# LCmeter0-LCD3310-PICCOMP.net
KiCad netlist of a schematic drawn in EAGLE
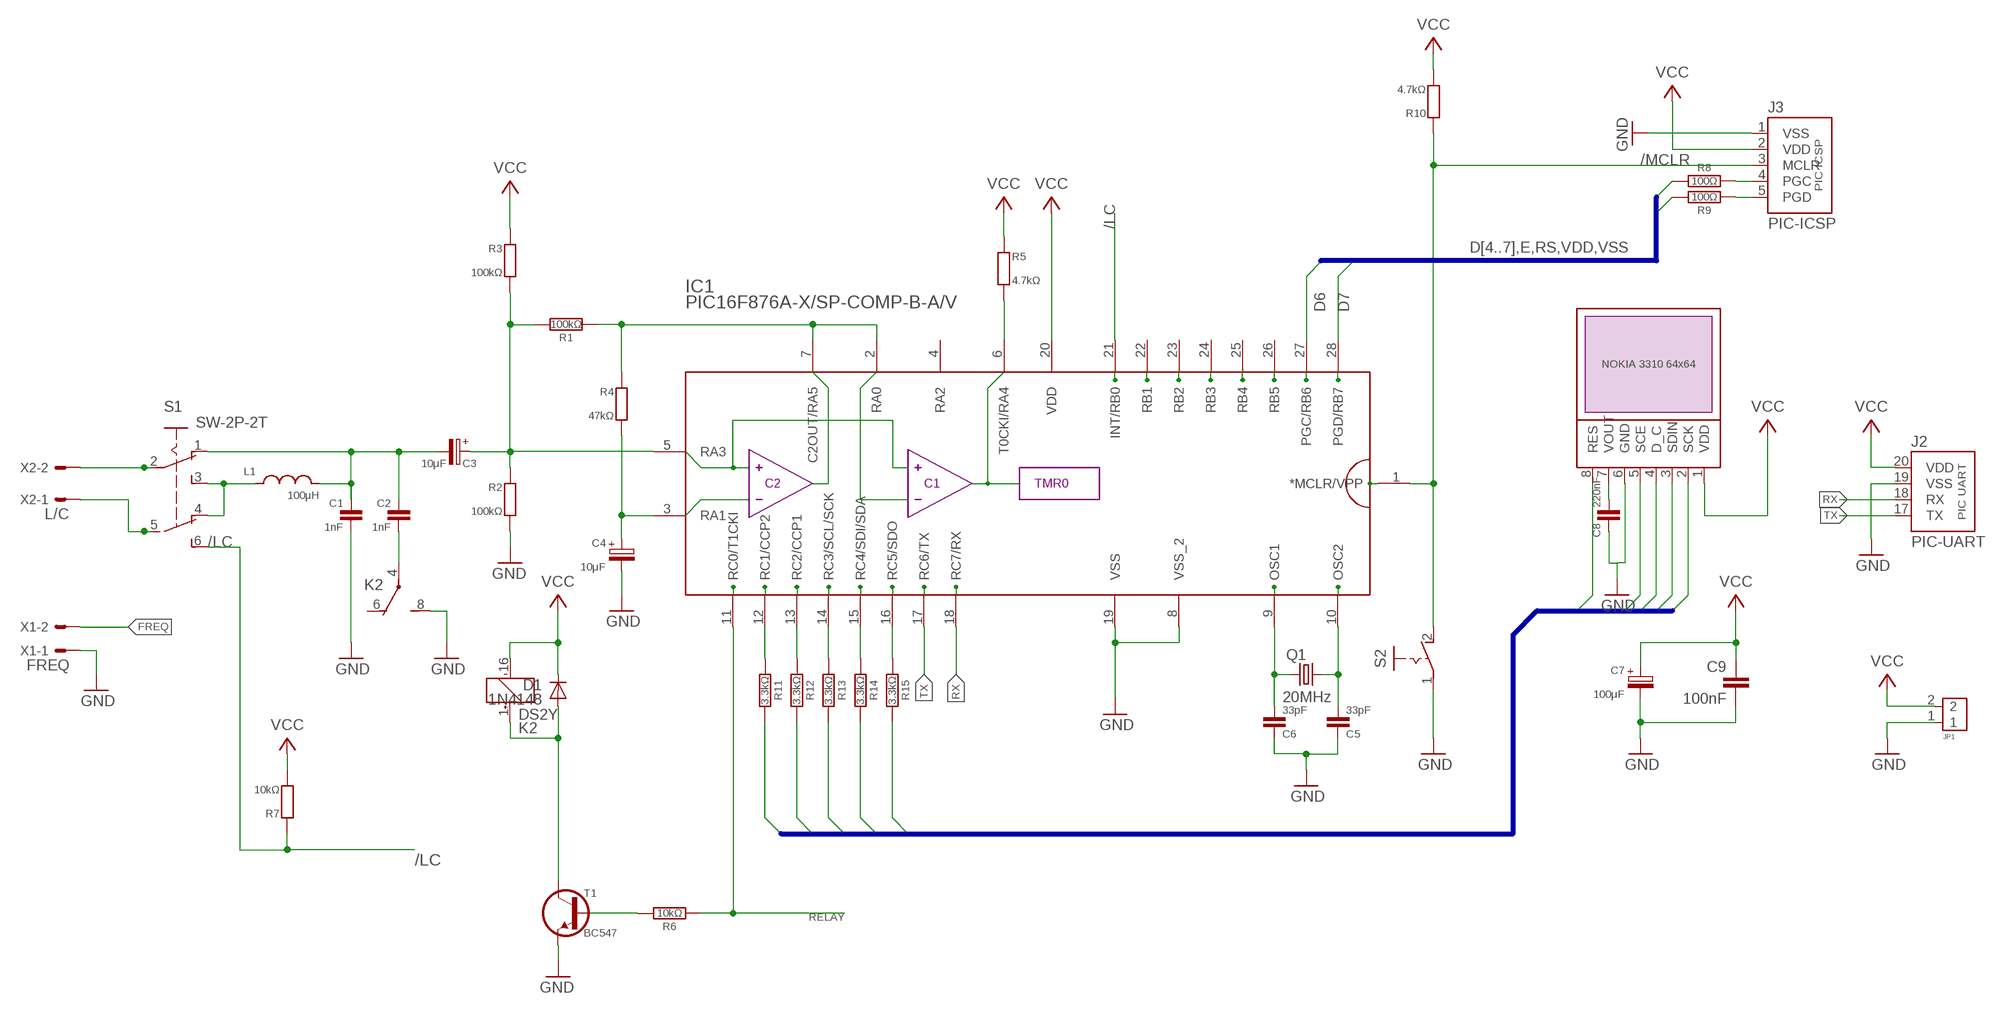
[diagram p0: schematic, sheet 1]

(export (version "E")
  (design (tool "Eeschema 10.0.6"))
  (components
    (comp (ref "C1")
      (value "1nF")
      (footprint "eagle-import:C050-020X036")
      (libsource (lib "eagle-import") (part "C050-020X036"))
    )
    (comp (ref "C2")
      (value "1nF")
      (footprint "eagle-import:C050-020X036")
      (libsource (lib "eagle-import") (part "C050-020X036"))
    )
    (comp (ref "C3")
      (value "10μF")
      (footprint "eagle-import:E2,5-4")
      (libsource (lib "eagle-import") (part "CPOL-HE2,5-4"))
    )
    (comp (ref "C4")
      (value "10μF")
      (footprint "eagle-import:E2,5-4")
      (libsource (lib "eagle-import") (part "CPOLE2,5-4"))
    )
    (comp (ref "C5")
      (value "33pF")
      (footprint "eagle-import:C025-020X036")
      (libsource (lib "eagle-import") (part "C025-020X036"))
    )
    (comp (ref "C6")
      (value "33pF")
      (footprint "eagle-import:C025-020X036")
      (libsource (lib "eagle-import") (part "C025-020X036"))
    )
    (comp (ref "C7")
      (value "100μF")
      (footprint "eagle-import:E2,5-5")
      (libsource (lib "eagle-import") (part "CPOLE2.5-5"))
    )
    (comp (ref "C8")
      (value "220nF")
      (footprint "eagle-import:C050-020X044_V")
      (libsource (lib "eagle-import") (part "C-H050-020X044/V"))
    )
    (comp (ref "C9")
      (value "100nF")
      (footprint "eagle-import:C025-024X044")
      (libsource (lib "eagle-import") (part "C-EU025-024X044"))
    )
    (comp (ref "D1")
      (value "1N4148")
      (footprint "eagle-import:DO34-7")
      (libsource (lib "eagle-import") (part "1N414834-7"))
    )
    (comp (ref "IC1")
      (value "PIC16F876A-X/SP-COMP-B-A/V")
      (footprint "eagle-import:DIL28-3_V")
      (libsource (lib "eagle-import") (part "PIC16F876A-X/SP-COMP-B-A/V"))
    )
    (comp (ref "J2")
      (value "PIC-UART")
      (footprint "eagle-import:PIC-UART")
      (libsource (lib "eagle-import") (part "PIC-UART"))
    )
    (comp (ref "J3")
      (value "PIC-ICSP")
      (footprint "eagle-import:CONN-5P")
      (libsource (lib "eagle-import") (part "PIC-ICSP"))
    )
    (comp (ref "JP1")
      (value "CONN-2P2P/V")
      (footprint "eagle-import:CONN-2P-V")
      (libsource (lib "eagle-import") (part "CONN-2P2P/V"))
    )
    (comp (ref "K2")
      (value "DS2Y")
      (footprint "eagle-import:DS2Y")
      (fields (field (name "MPN") "DS2Y-S-DC5V"))
      (libsource (lib "eagle-import") (part "DS2Y-S-DC5V"))
    )
    (comp (ref "L1")
      (value "100µH")
      (footprint "eagle-import:L-02_5V")
      (libsource (lib "eagle-import") (part "L-SHORT02/5"))
    )
    (comp (ref "LCD1")
      (value "NOKIA-3310-64X64")
      (footprint "eagle-import:1X8")
      (libsource (lib "eagle-import") (part "NOKIA-3310-64X64"))
    )
    (comp (ref "Q1")
      (value "20MHz")
      (footprint "eagle-import:HC49")
      (libsource (lib "eagle-import") (part "CRYSTALHC49"))
    )
    (comp (ref "R1")
      (value "100kΩ")
      (footprint "eagle-import:0204_10")
      (libsource (lib "eagle-import") (part "R-H0204/10"))
    )
    (comp (ref "R2")
      (value "100kΩ")
      (footprint "eagle-import:0204_10")
      (libsource (lib "eagle-import") (part "R0204/10"))
    )
    (comp (ref "R3")
      (value "100kΩ")
      (footprint "eagle-import:0204_10")
      (libsource (lib "eagle-import") (part "R0204/10"))
    )
    (comp (ref "R4")
      (value "47kΩ")
      (footprint "eagle-import:0204_10")
      (libsource (lib "eagle-import") (part "R0204/10"))
    )
    (comp (ref "R5")
      (value "4.7kΩ")
      (footprint "eagle-import:0204_10")
      (libsource (lib "eagle-import") (part "R0204/10"))
    )
    (comp (ref "R6")
      (value "10kΩ")
      (footprint "eagle-import:0204_10")
      (libsource (lib "eagle-import") (part "R-H0204/10"))
    )
    (comp (ref "R7")
      (value "10kΩ")
      (footprint "eagle-import:0204_10-V")
      (libsource (lib "eagle-import") (part "R0204/10-V"))
    )
    (comp (ref "R8")
      (value "100Ω")
      (footprint "eagle-import:0204_10")
      (libsource (lib "eagle-import") (part "R-H0204/10"))
    )
    (comp (ref "R9")
      (value "100Ω")
      (footprint "eagle-import:0204_10")
      (libsource (lib "eagle-import") (part "R-H0204/10"))
    )
    (comp (ref "R10")
      (value "4.7kΩ")
      (footprint "eagle-import:0204_10")
      (libsource (lib "eagle-import") (part "R0204/10"))
    )
    (comp (ref "R11")
      (value "3.3kΩ")
      (footprint "eagle-import:0204_10")
      (libsource (lib "eagle-import") (part "R-H0204/10"))
    )
    (comp (ref "R12")
      (value "3.3kΩ")
      (footprint "eagle-import:0204_10")
      (libsource (lib "eagle-import") (part "R-H0204/10"))
    )
    (comp (ref "R13")
      (value "3.3kΩ")
      (footprint "eagle-import:0204_10")
      (libsource (lib "eagle-import") (part "R-H0204/10"))
    )
    (comp (ref "R14")
      (value "3.3kΩ")
      (footprint "eagle-import:0204_10")
      (libsource (lib "eagle-import") (part "R-H0204/10"))
    )
    (comp (ref "R15")
      (value "3.3kΩ")
      (footprint "eagle-import:0204_10")
      (libsource (lib "eagle-import") (part "R-H0204/10"))
    )
    (comp (ref "S1")
      (value "SW-2P-2T")
      (footprint "eagle-import:SLSW-2P2T")
      (libsource (lib "eagle-import") (part "SW-2P-2T"))
    )
    (comp (ref "S2")
      (value "PB-1P-1T")
      (footprint "eagle-import:PB-1P1T")
      (libsource (lib "eagle-import") (part "PB-1P-1T"))
    )
    (comp (ref "T1")
      (value "BC547")
      (footprint "eagle-import:TO92-CBE")
      (libsource (lib "eagle-import") (part "BC547"))
    )
    (comp (ref "X1")
      (value "FREQ")
      (footprint "eagle-import:70543-02")
      (libsource (lib "eagle-import") (part "C-GRID-02-70543"))
    )
    (comp (ref "X2")
      (value "L/C")
      (footprint "eagle-import:70543-02")
      (libsource (lib "eagle-import") (part "C-GRID-02-70543"))
    )
  )
  (nets
    (net (code "5") (name "/D6") (class "Default")
      (node (ref "IC1") (pin "27") (pinfunction "PGC/RB6_27") (pintype "passive"))
      (node (ref "R9") (pin "1") (pinfunction "1_1") (pintype "passive"))
    )
    (net (code "6") (name "/D7") (class "Default")
      (node (ref "IC1") (pin "28") (pinfunction "PGD/RB7_28") (pintype "passive"))
      (node (ref "R8") (pin "1") (pinfunction "1_1") (pintype "passive"))
    )
    (net (code "7") (name "/D_C") (class "Default")
      (node (ref "LCD1") (pin "4") (pinfunction "D_C_4") (pintype "passive"))
      (node (ref "R13") (pin "1") (pinfunction "1_1") (pintype "passive"))
    )
    (net (code "8") (name "/RELAY") (class "Default")
      (node (ref "IC1") (pin "11") (pinfunction "RC0/T1CKI_11") (pintype "passive"))
      (node (ref "R6") (pin "2") (pinfunction "2_2") (pintype "passive"))
    )
    (net (code "9") (name "/RES") (class "Default")
      (node (ref "LCD1") (pin "8") (pinfunction "RES_8") (pintype "passive"))
      (node (ref "R11") (pin "1") (pinfunction "1_1") (pintype "passive"))
    )
    (net (code "10") (name "/SCE") (class "Default")
      (node (ref "LCD1") (pin "5") (pinfunction "SCE_5") (pintype "passive"))
      (node (ref "R12") (pin "1") (pinfunction "1_1") (pintype "passive"))
    )
    (net (code "11") (name "/SCLK") (class "Default")
      (node (ref "LCD1") (pin "2") (pinfunction "SCK_2") (pintype "passive"))
      (node (ref "R15") (pin "1") (pinfunction "1_1") (pintype "passive"))
    )
    (net (code "12") (name "/SDIN") (class "Default")
      (node (ref "LCD1") (pin "3") (pinfunction "SDIN_3") (pintype "passive"))
      (node (ref "R14") (pin "1") (pinfunction "1_1") (pintype "passive"))
    )
    (net (code "14") (name "/{slash}LC") (class "Default")
      (node (ref "IC1") (pin "21") (pinfunction "INT/RB0_21") (pintype "passive"))
      (node (ref "R7") (pin "1") (pinfunction "1_1") (pintype "passive"))
      (node (ref "S1") (pin "6") (pinfunction "S1_6") (pintype "passive"))
    )
    (net (code "15") (name "/{slash}MCLR") (class "Default")
      (node (ref "IC1") (pin "1") (pinfunction "*MCLR/VPP_1") (pintype "passive"))
      (node (ref "J3") (pin "3") (pinfunction "MCLR_3") (pintype "passive"))
      (node (ref "R10") (pin "1") (pinfunction "1_1") (pintype "passive"))
      (node (ref "S2") (pin "2") (pinfunction "S_2") (pintype "passive"))
    )
    (net (code "16") (name "FREQ") (class "Default")
      (node (ref "X1") (pin "2") (pinfunction "S_2") (pintype "passive"))
    )
    (net (code "17") (name "GND") (class "Default")
      (node (ref "C1") (pin "2") (pinfunction "2_2") (pintype "passive"))
      (node (ref "C4") (pin "-") (pinfunction "-_-") (pintype "passive"))
      (node (ref "C5") (pin "1") (pinfunction "1_1") (pintype "passive"))
      (node (ref "C6") (pin "1") (pinfunction "1_1") (pintype "passive"))
      (node (ref "C7") (pin "-") (pinfunction "-_-") (pintype "passive"))
      (node (ref "C8") (pin "1") (pinfunction "1_1") (pintype "passive"))
      (node (ref "C9") (pin "2") (pinfunction "2_2") (pintype "passive"))
      (node (ref "IC1") (pin "19") (pinfunction "VSS_19") (pintype "passive"))
      (node (ref "IC1") (pin "8") (pinfunction "VSS_2_8") (pintype "passive"))
      (node (ref "J2") (pin "19") (pinfunction "VSS_19") (pintype "passive"))
      (node (ref "J3") (pin "1") (pinfunction "VSS_1") (pintype "passive"))
      (node (ref "JP1") (pin "1") (pinfunction "1_1") (pintype "bidirectional"))
      (node (ref "K2") (pin "8") (pinfunction "S_8") (pintype "passive"))
      (node (ref "LCD1") (pin "6") (pinfunction "GND_6") (pintype "passive"))
      (node (ref "R2") (pin "2") (pinfunction "2_2") (pintype "passive"))
      (node (ref "S2") (pin "1") (pinfunction "P_1") (pintype "passive"))
      (node (ref "T1") (pin "E") (pinfunction "E_E") (pintype "passive"))
      (node (ref "X1") (pin "1") (pinfunction "S_1") (pintype "passive"))
    )
    (net (code "18") (name "Net-(IC1-C2OUT{slash}RA5)") (class "Default")
      (node (ref "IC1") (pin "2") (pinfunction "RA0_2") (pintype "passive"))
      (node (ref "IC1") (pin "7") (pinfunction "C2OUT/RA5_7") (pintype "passive"))
      (node (ref "R1") (pin "1") (pinfunction "1_1") (pintype "passive"))
      (node (ref "R4") (pin "1") (pinfunction "1_1") (pintype "passive"))
    )
    (net (code "19") (name "Net-(IC1-OSC1)") (class "Default")
      (node (ref "C6") (pin "2") (pinfunction "2_2") (pintype "passive"))
      (node (ref "IC1") (pin "9") (pinfunction "OSC1_9") (pintype "passive"))
      (node (ref "Q1") (pin "1") (pinfunction "1_1") (pintype "passive"))
    )
    (net (code "20") (name "Net-(IC1-OSC2)") (class "Default")
      (node (ref "C5") (pin "2") (pinfunction "2_2") (pintype "passive"))
      (node (ref "IC1") (pin "10") (pinfunction "OSC2_10") (pintype "passive"))
      (node (ref "Q1") (pin "2") (pinfunction "2_2") (pintype "passive"))
    )
    (net (code "21") (name "Net-(IC1-RA1)") (class "Default")
      (node (ref "C4") (pin "+") (pinfunction "+_+") (pintype "passive"))
      (node (ref "IC1") (pin "3") (pinfunction "RA1_3") (pintype "passive"))
      (node (ref "R4") (pin "2") (pinfunction "2_2") (pintype "passive"))
    )
    (net (code "22") (name "Net-(IC1-RA3)") (class "Default")
      (node (ref "C3") (pin "+") (pinfunction "+_+") (pintype "passive"))
      (node (ref "IC1") (pin "5") (pinfunction "RA3_5") (pintype "passive"))
      (node (ref "R1") (pin "2") (pinfunction "2_2") (pintype "passive"))
      (node (ref "R2") (pin "1") (pinfunction "1_1") (pintype "passive"))
      (node (ref "R3") (pin "2") (pinfunction "2_2") (pintype "passive"))
    )
    (net (code "23") (name "Net-(IC1-RC1{slash}CCP2)") (class "Default")
      (node (ref "IC1") (pin "12") (pinfunction "RC1/CCP2_12") (pintype "passive"))
      (node (ref "R11") (pin "2") (pinfunction "2_2") (pintype "passive"))
    )
    (net (code "24") (name "Net-(IC1-RC2{slash}CCP1)") (class "Default")
      (node (ref "IC1") (pin "13") (pinfunction "RC2/CCP1_13") (pintype "passive"))
      (node (ref "R12") (pin "2") (pinfunction "2_2") (pintype "passive"))
    )
    (net (code "25") (name "Net-(IC1-RC3{slash}SCL{slash}SCK)") (class "Default")
      (node (ref "IC1") (pin "14") (pinfunction "RC3/SCL/SCK_14") (pintype "passive"))
      (node (ref "R13") (pin "2") (pinfunction "2_2") (pintype "passive"))
    )
    (net (code "26") (name "Net-(IC1-RC4{slash}SDI{slash}SDA)") (class "Default")
      (node (ref "IC1") (pin "15") (pinfunction "RC4/SDI/SDA_15") (pintype "passive"))
      (node (ref "R14") (pin "2") (pinfunction "2_2") (pintype "passive"))
    )
    (net (code "27") (name "Net-(IC1-RC5{slash}SDO)") (class "Default")
      (node (ref "IC1") (pin "16") (pinfunction "RC5/SDO_16") (pintype "passive"))
      (node (ref "R15") (pin "2") (pinfunction "2_2") (pintype "passive"))
    )
    (net (code "28") (name "Net-(IC1-T0CKI{slash}RA4)") (class "Default")
      (node (ref "IC1") (pin "6") (pinfunction "T0CKI/RA4_6") (pintype "passive"))
      (node (ref "R5") (pin "2") (pinfunction "2_2") (pintype "passive"))
    )
    (net (code "29") (name "Net-(J3-PGC)") (class "Default")
      (node (ref "J3") (pin "4") (pinfunction "PGC_4") (pintype "passive"))
      (node (ref "R8") (pin "2") (pinfunction "2_2") (pintype "passive"))
    )
    (net (code "30") (name "Net-(J3-PGD)") (class "Default")
      (node (ref "J3") (pin "5") (pinfunction "PGD_5") (pintype "passive"))
      (node (ref "R9") (pin "2") (pinfunction "2_2") (pintype "passive"))
    )
    (net (code "31") (name "Net-(K2A-+)") (class "Default")
      (node (ref "D1") (pin "A") (pinfunction "A_A") (pintype "passive"))
      (node (ref "K2") (pin "1") (pinfunction "+_1") (pintype "passive"))
      (node (ref "T1") (pin "C") (pinfunction "C_C") (pintype "passive"))
    )
    (net (code "32") (name "Net-(K2B-P)") (class "Default")
      (node (ref "C2") (pin "2") (pinfunction "2_2") (pintype "passive"))
      (node (ref "K2") (pin "4") (pinfunction "P_4") (pintype "passive"))
    )
    (net (code "33") (name "Net-(LCD1-VOUT)") (class "Default")
      (node (ref "C8") (pin "2") (pinfunction "2_2") (pintype "passive"))
      (node (ref "LCD1") (pin "7") (pinfunction "VOUT_7") (pintype "passive"))
    )
    (net (code "34") (name "Net-(R6-Pad1)") (class "Default")
      (node (ref "R6") (pin "1") (pinfunction "1_1") (pintype "passive"))
      (node (ref "T1") (pin "B") (pinfunction "B_B") (pintype "passive"))
    )
    (net (code "35") (name "Net-(S1-O)") (class "Default")
      (node (ref "C1") (pin "1") (pinfunction "1_1") (pintype "passive"))
      (node (ref "C2") (pin "1") (pinfunction "1_1") (pintype "passive"))
      (node (ref "C3") (pin "-") (pinfunction "-_-") (pintype "passive"))
      (node (ref "L1") (pin "2") (pinfunction "2_2") (pintype "passive"))
      (node (ref "S1") (pin "1") (pinfunction "O_1") (pintype "passive"))
    )
    (net (code "36") (name "Net-(S1-O1)") (class "Default")
      (node (ref "L1") (pin "1") (pinfunction "1_1") (pintype "passive"))
      (node (ref "S1") (pin "3") (pinfunction "S_3") (pintype "passive"))
      (node (ref "S1") (pin "4") (pinfunction "O1_4") (pintype "passive"))
    )
    (net (code "37") (name "Net-(S1-P)") (class "Default")
      (node (ref "S1") (pin "2") (pinfunction "P_2") (pintype "passive"))
      (node (ref "X2") (pin "2") (pinfunction "S_2") (pintype "passive"))
    )
    (net (code "38") (name "Net-(S1-P1)") (class "Default")
      (node (ref "S1") (pin "5") (pinfunction "P1_5") (pintype "passive"))
      (node (ref "X2") (pin "1") (pinfunction "S_1") (pintype "passive"))
    )
    (net (code "39") (name "RX") (class "Default")
      (node (ref "IC1") (pin "18") (pinfunction "RC7/RX_18") (pintype "passive"))
      (node (ref "J2") (pin "18") (pinfunction "RX_18") (pintype "passive"))
    )
    (net (code "40") (name "TX") (class "Default")
      (node (ref "IC1") (pin "17") (pinfunction "RC6/TX_17") (pintype "passive"))
      (node (ref "J2") (pin "17") (pinfunction "TX_17") (pintype "passive"))
    )
    (net (code "41") (name "VCC") (class "Default")
      (node (ref "C7") (pin "+") (pinfunction "+_+") (pintype "passive"))
      (node (ref "C9") (pin "1") (pinfunction "1_1") (pintype "passive"))
      (node (ref "D1") (pin "C") (pinfunction "C_C") (pintype "passive"))
      (node (ref "IC1") (pin "20") (pinfunction "VDD_20") (pintype "passive"))
      (node (ref "J2") (pin "20") (pinfunction "VDD_20") (pintype "passive"))
      (node (ref "J3") (pin "2") (pinfunction "VDD_2") (pintype "passive"))
      (node (ref "JP1") (pin "2") (pinfunction "2_2") (pintype "bidirectional"))
      (node (ref "K2") (pin "16") (pinfunction "-_16") (pintype "passive"))
      (node (ref "LCD1") (pin "1") (pinfunction "VDD_1") (pintype "passive"))
      (node (ref "R10") (pin "2") (pinfunction "2_2") (pintype "passive"))
      (node (ref "R3") (pin "1") (pinfunction "1_1") (pintype "passive"))
      (node (ref "R5") (pin "1") (pinfunction "1_1") (pintype "passive"))
      (node (ref "R7") (pin "2") (pinfunction "2_2") (pintype "passive"))
    )
    (net (code "42") (name "unconnected-(IC1-RA2-Pad4)") (class "Default")
      (node (ref "IC1") (pin "4") (pinfunction "RA2_4") (pintype "passive"))
    )
    (net (code "43") (name "unconnected-(IC1-RB1-Pad22)") (class "Default")
      (node (ref "IC1") (pin "22") (pinfunction "RB1_22") (pintype "passive"))
    )
    (net (code "44") (name "unconnected-(IC1-RB2-Pad23)") (class "Default")
      (node (ref "IC1") (pin "23") (pinfunction "RB2_23") (pintype "passive"))
    )
    (net (code "45") (name "unconnected-(IC1-RB3-Pad24)") (class "Default")
      (node (ref "IC1") (pin "24") (pinfunction "RB3_24") (pintype "passive"))
    )
    (net (code "46") (name "unconnected-(IC1-RB4-Pad25)") (class "Default")
      (node (ref "IC1") (pin "25") (pinfunction "RB4_25") (pintype "passive"))
    )
    (net (code "47") (name "unconnected-(IC1-RB5-Pad26)") (class "Default")
      (node (ref "IC1") (pin "26") (pinfunction "RB5_26") (pintype "passive"))
    )
    (net (code "48") (name "unconnected-(K2B-O-Pad6)") (class "Default")
      (node (ref "K2") (pin "6") (pinfunction "O_6") (pintype "passive"))
    )
  )
)
